# B_to_VM_Protection_Circuit.net
KiCad netlist of a schematic drawn in EAGLE
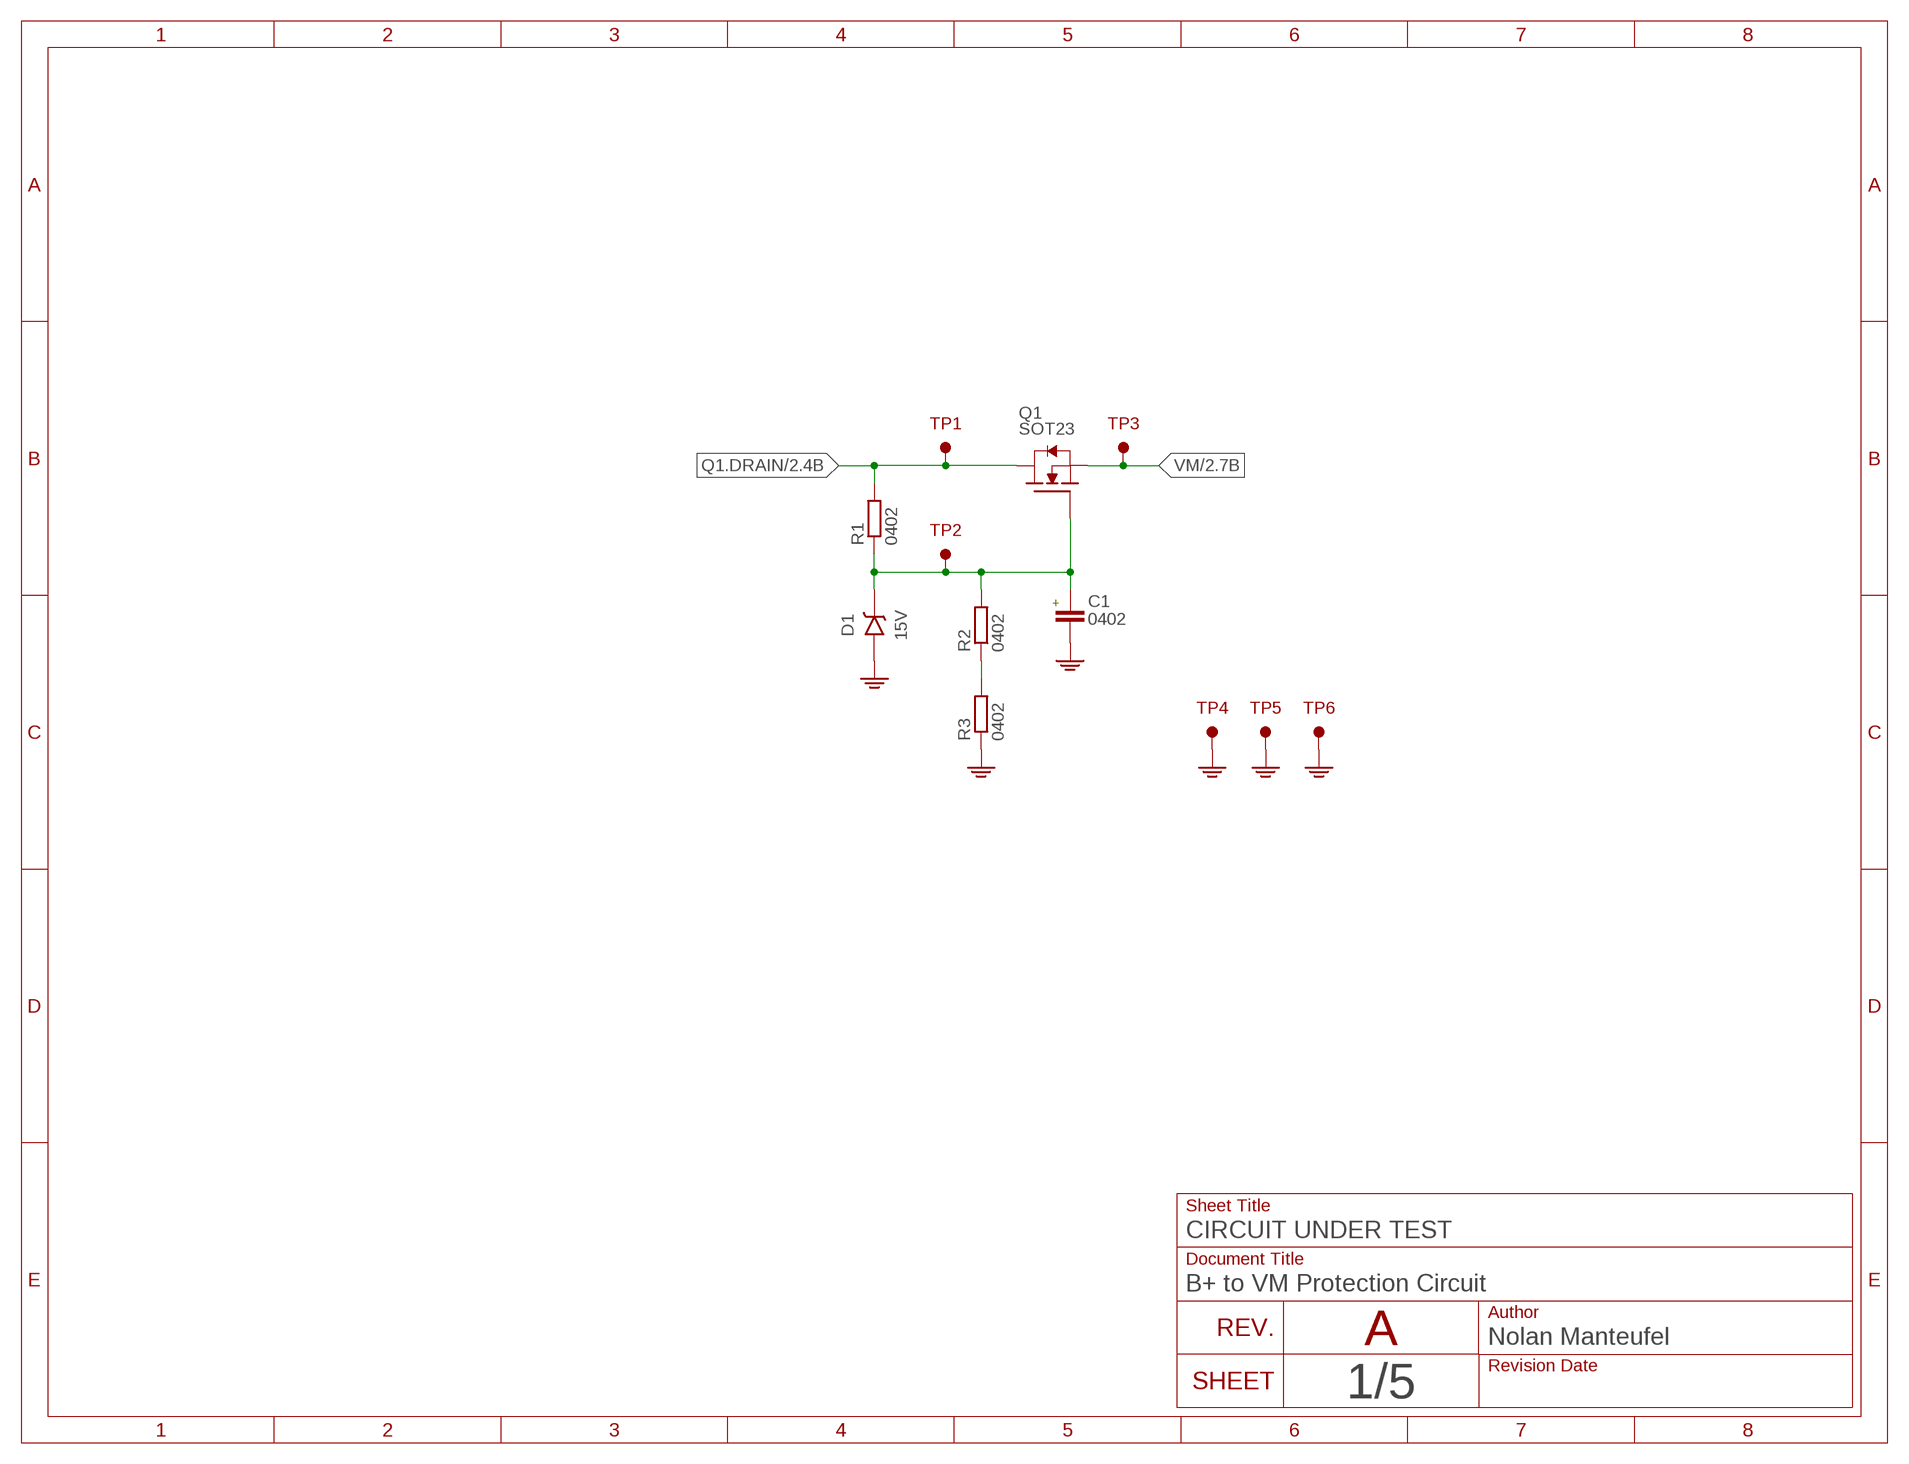
[diagram p0: schematic, sheet 1]
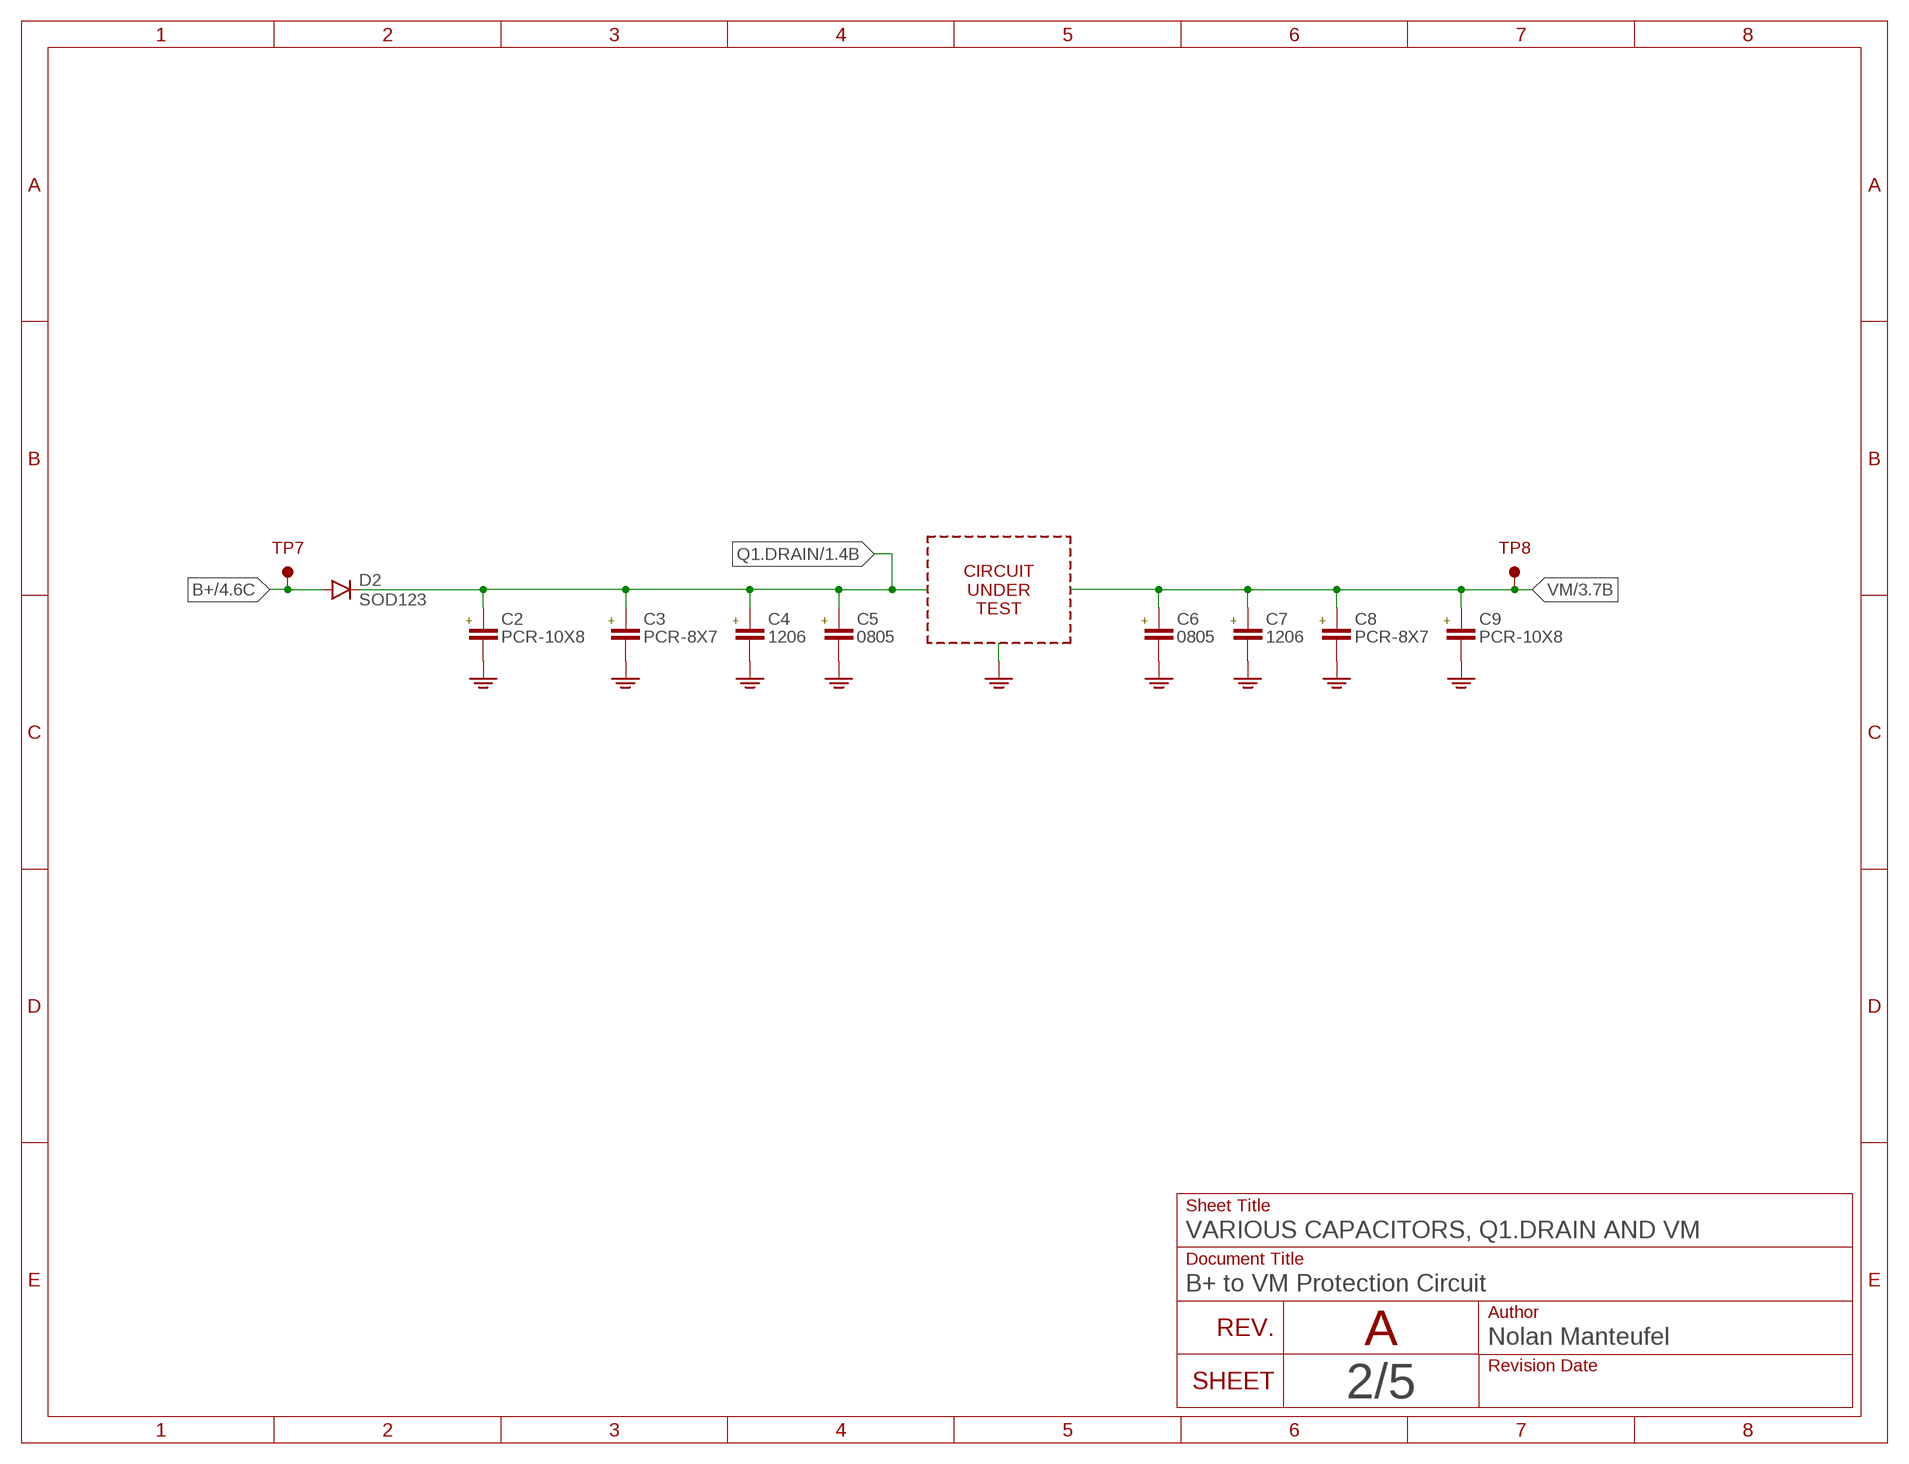
[diagram p1: schematic, sheet 2]
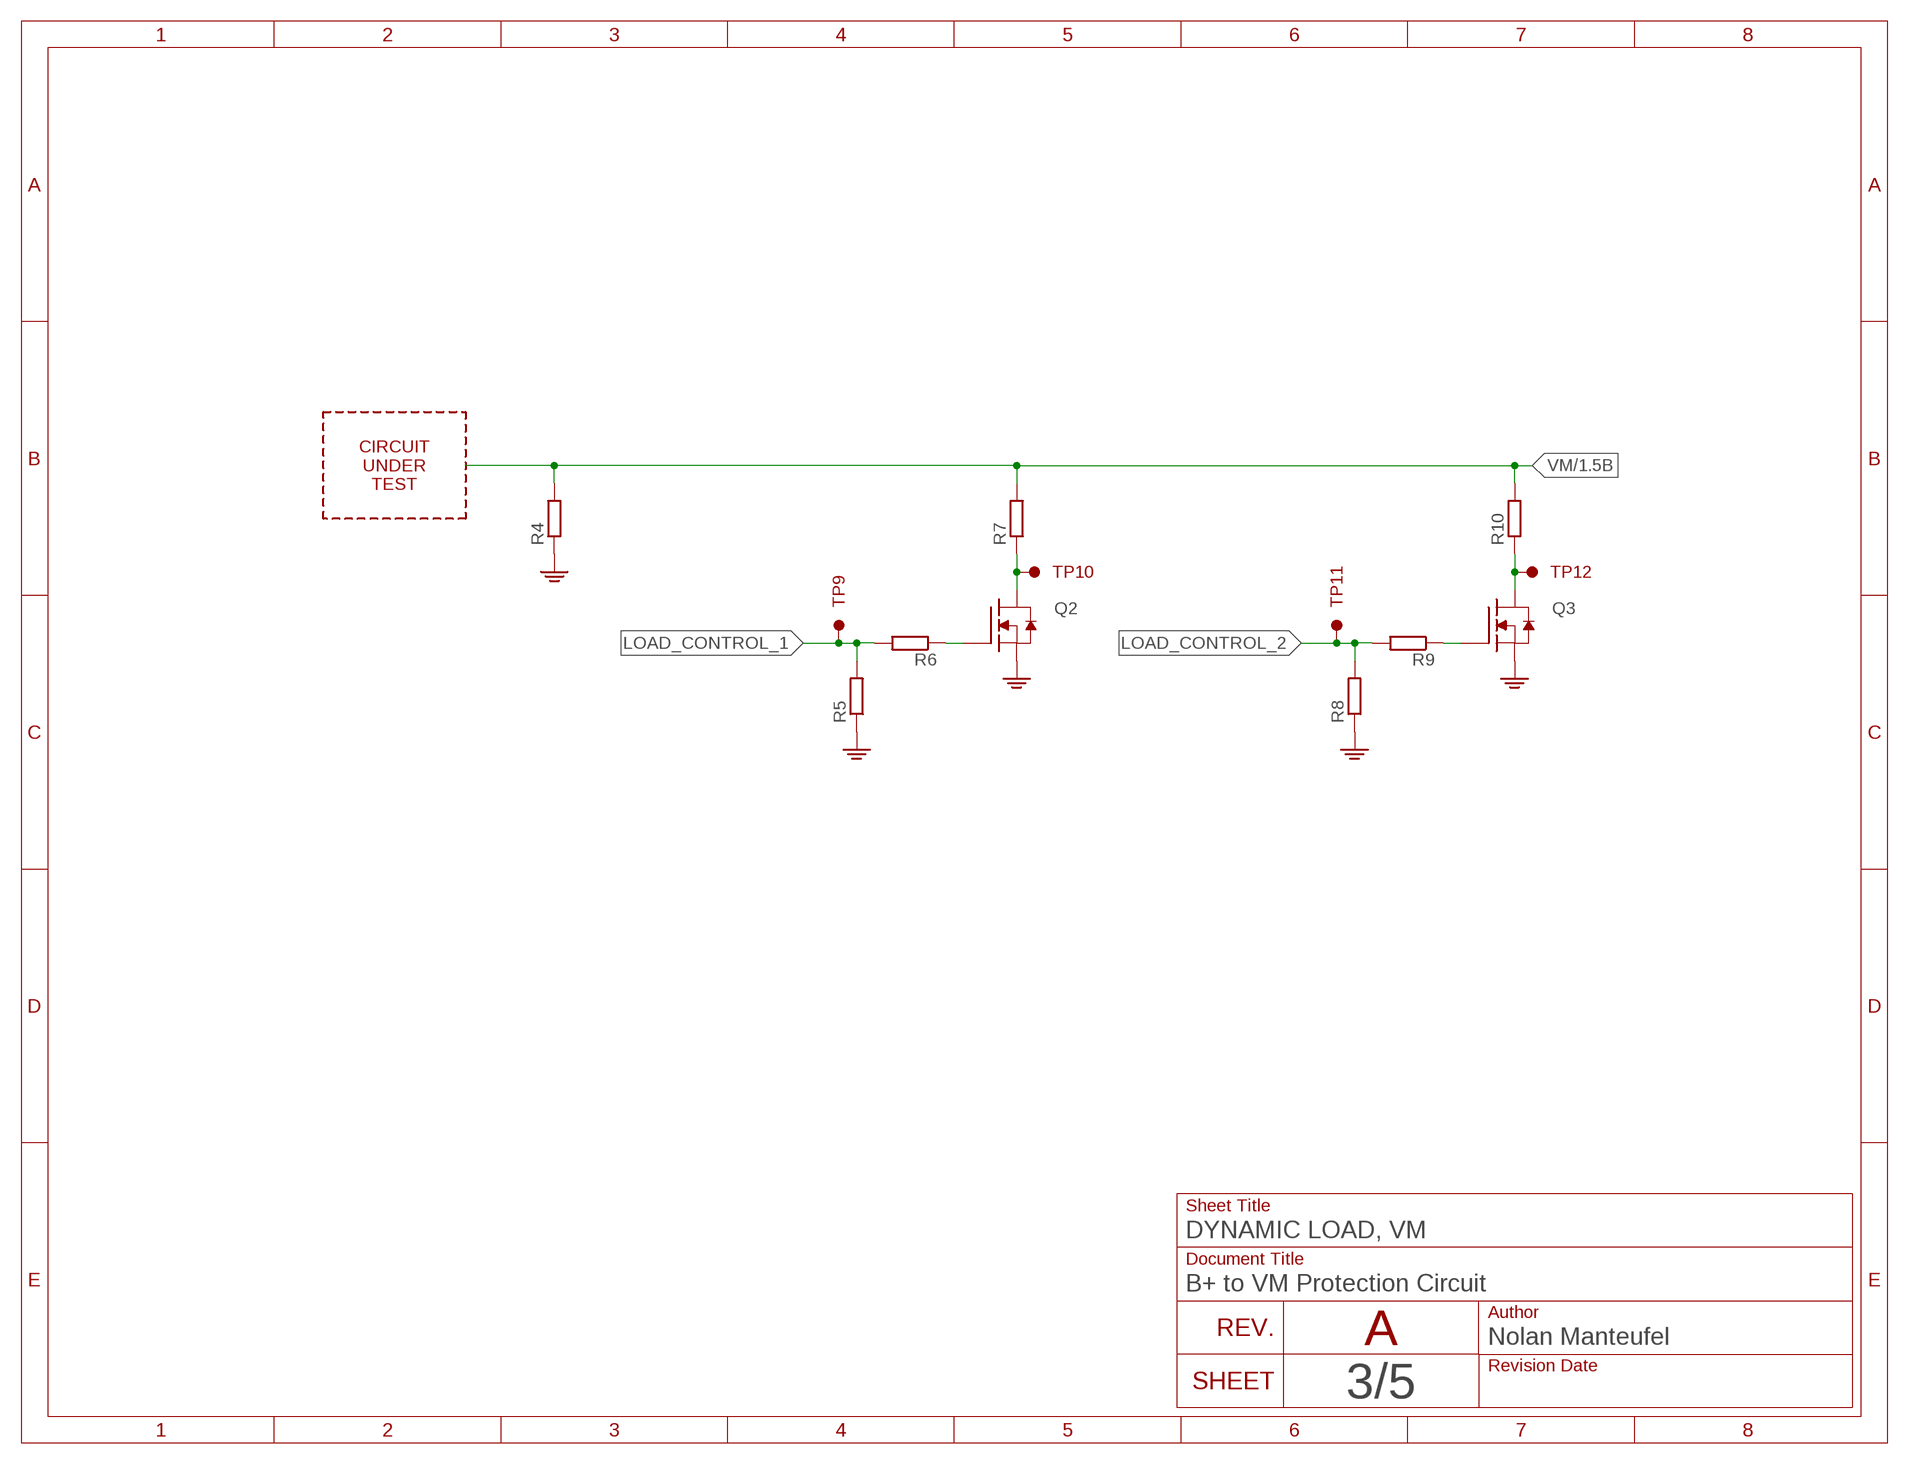
[diagram p2: schematic, sheet 3]
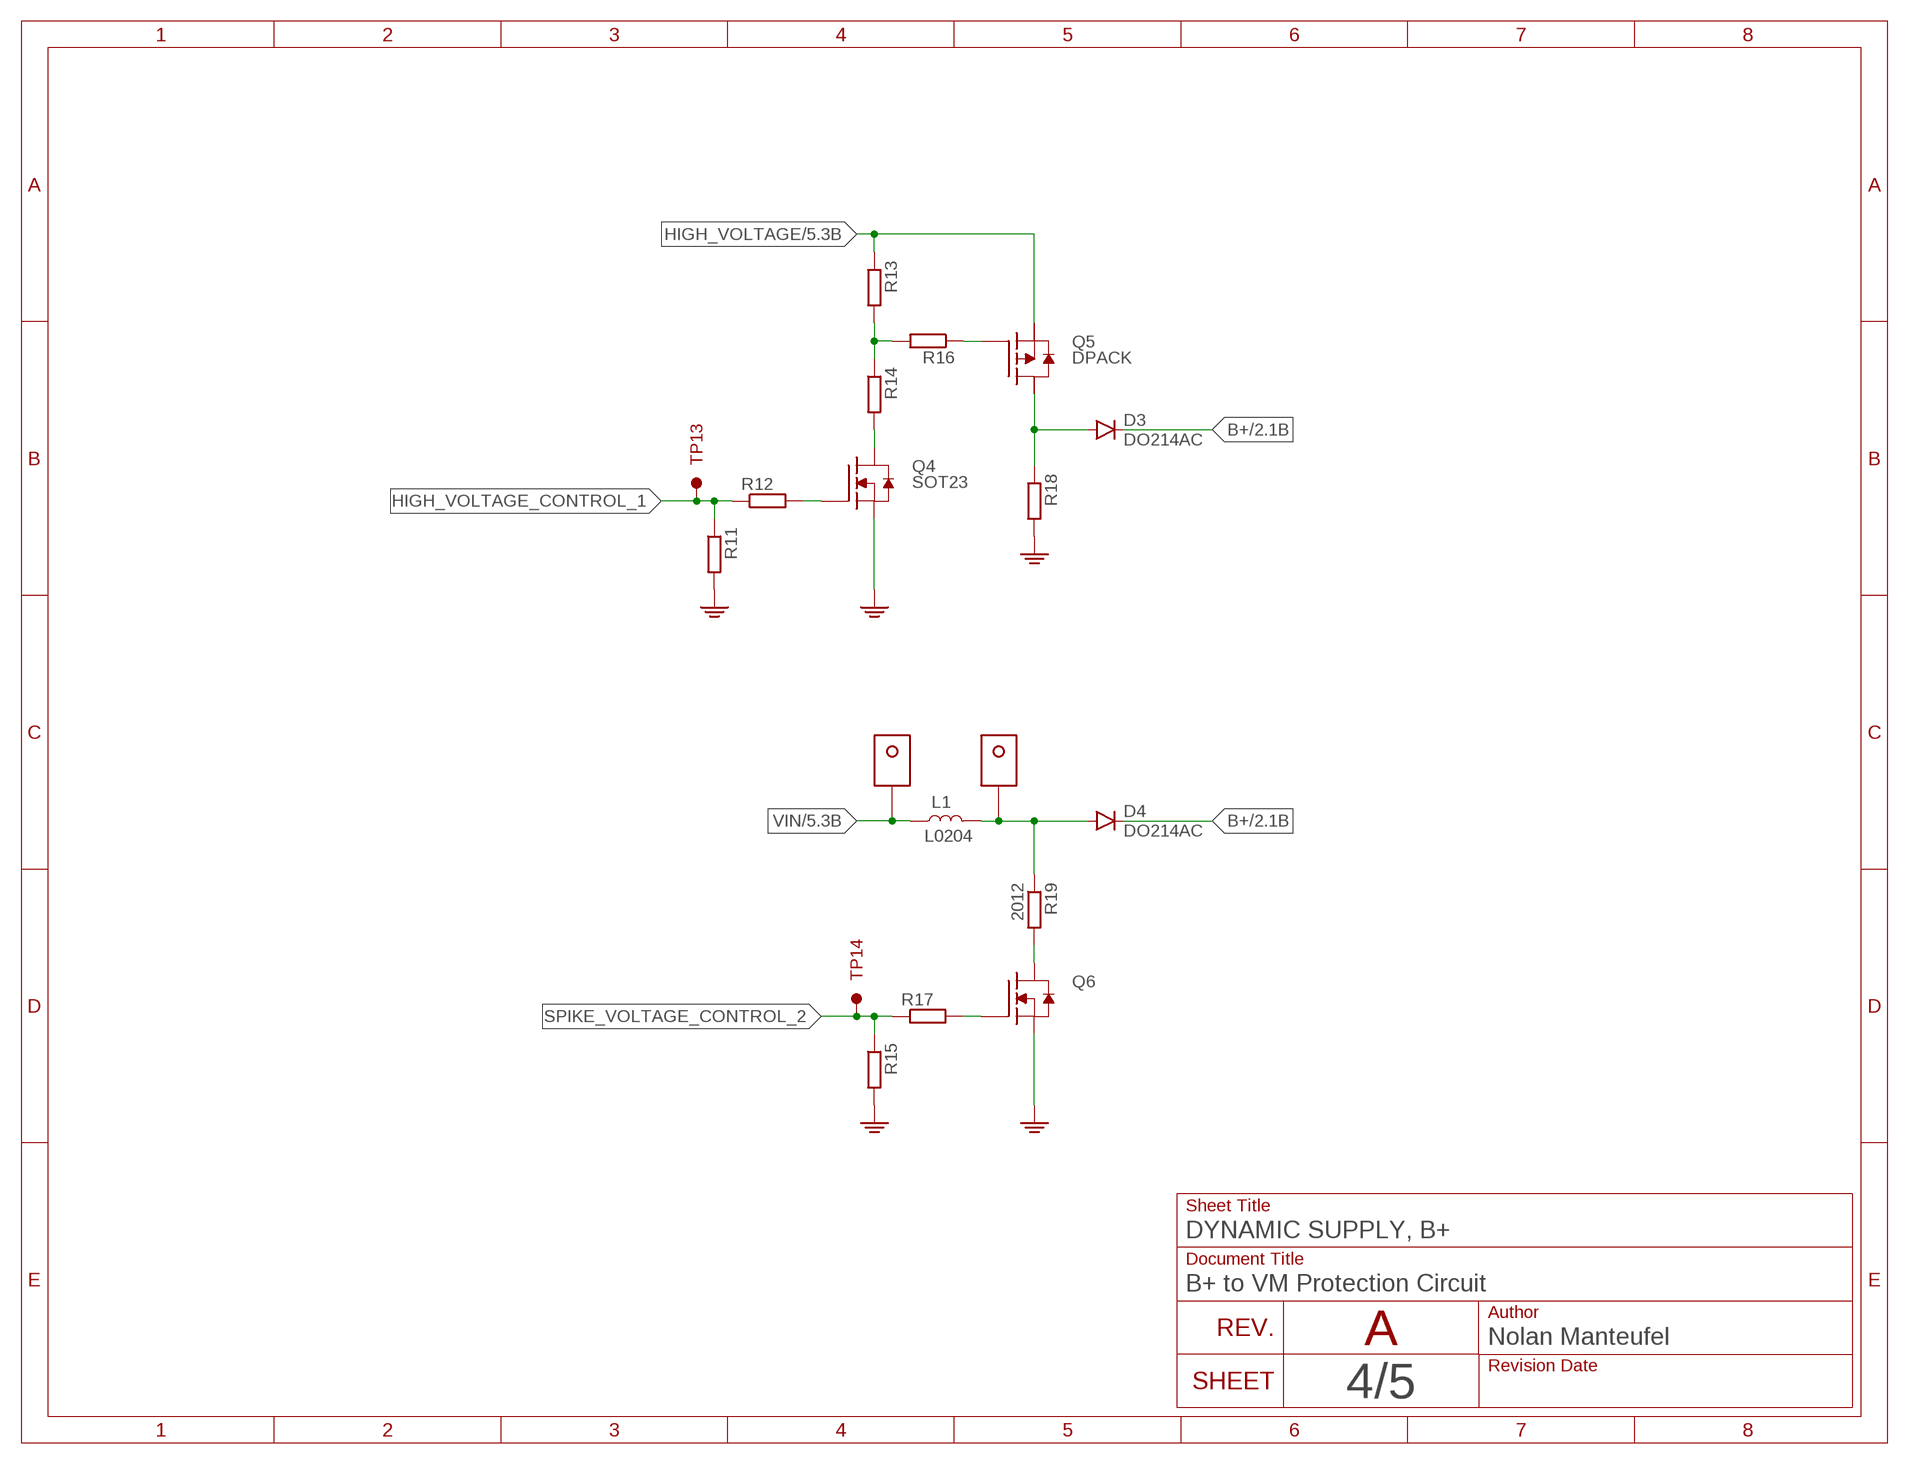
[diagram p3: schematic, sheet 4]
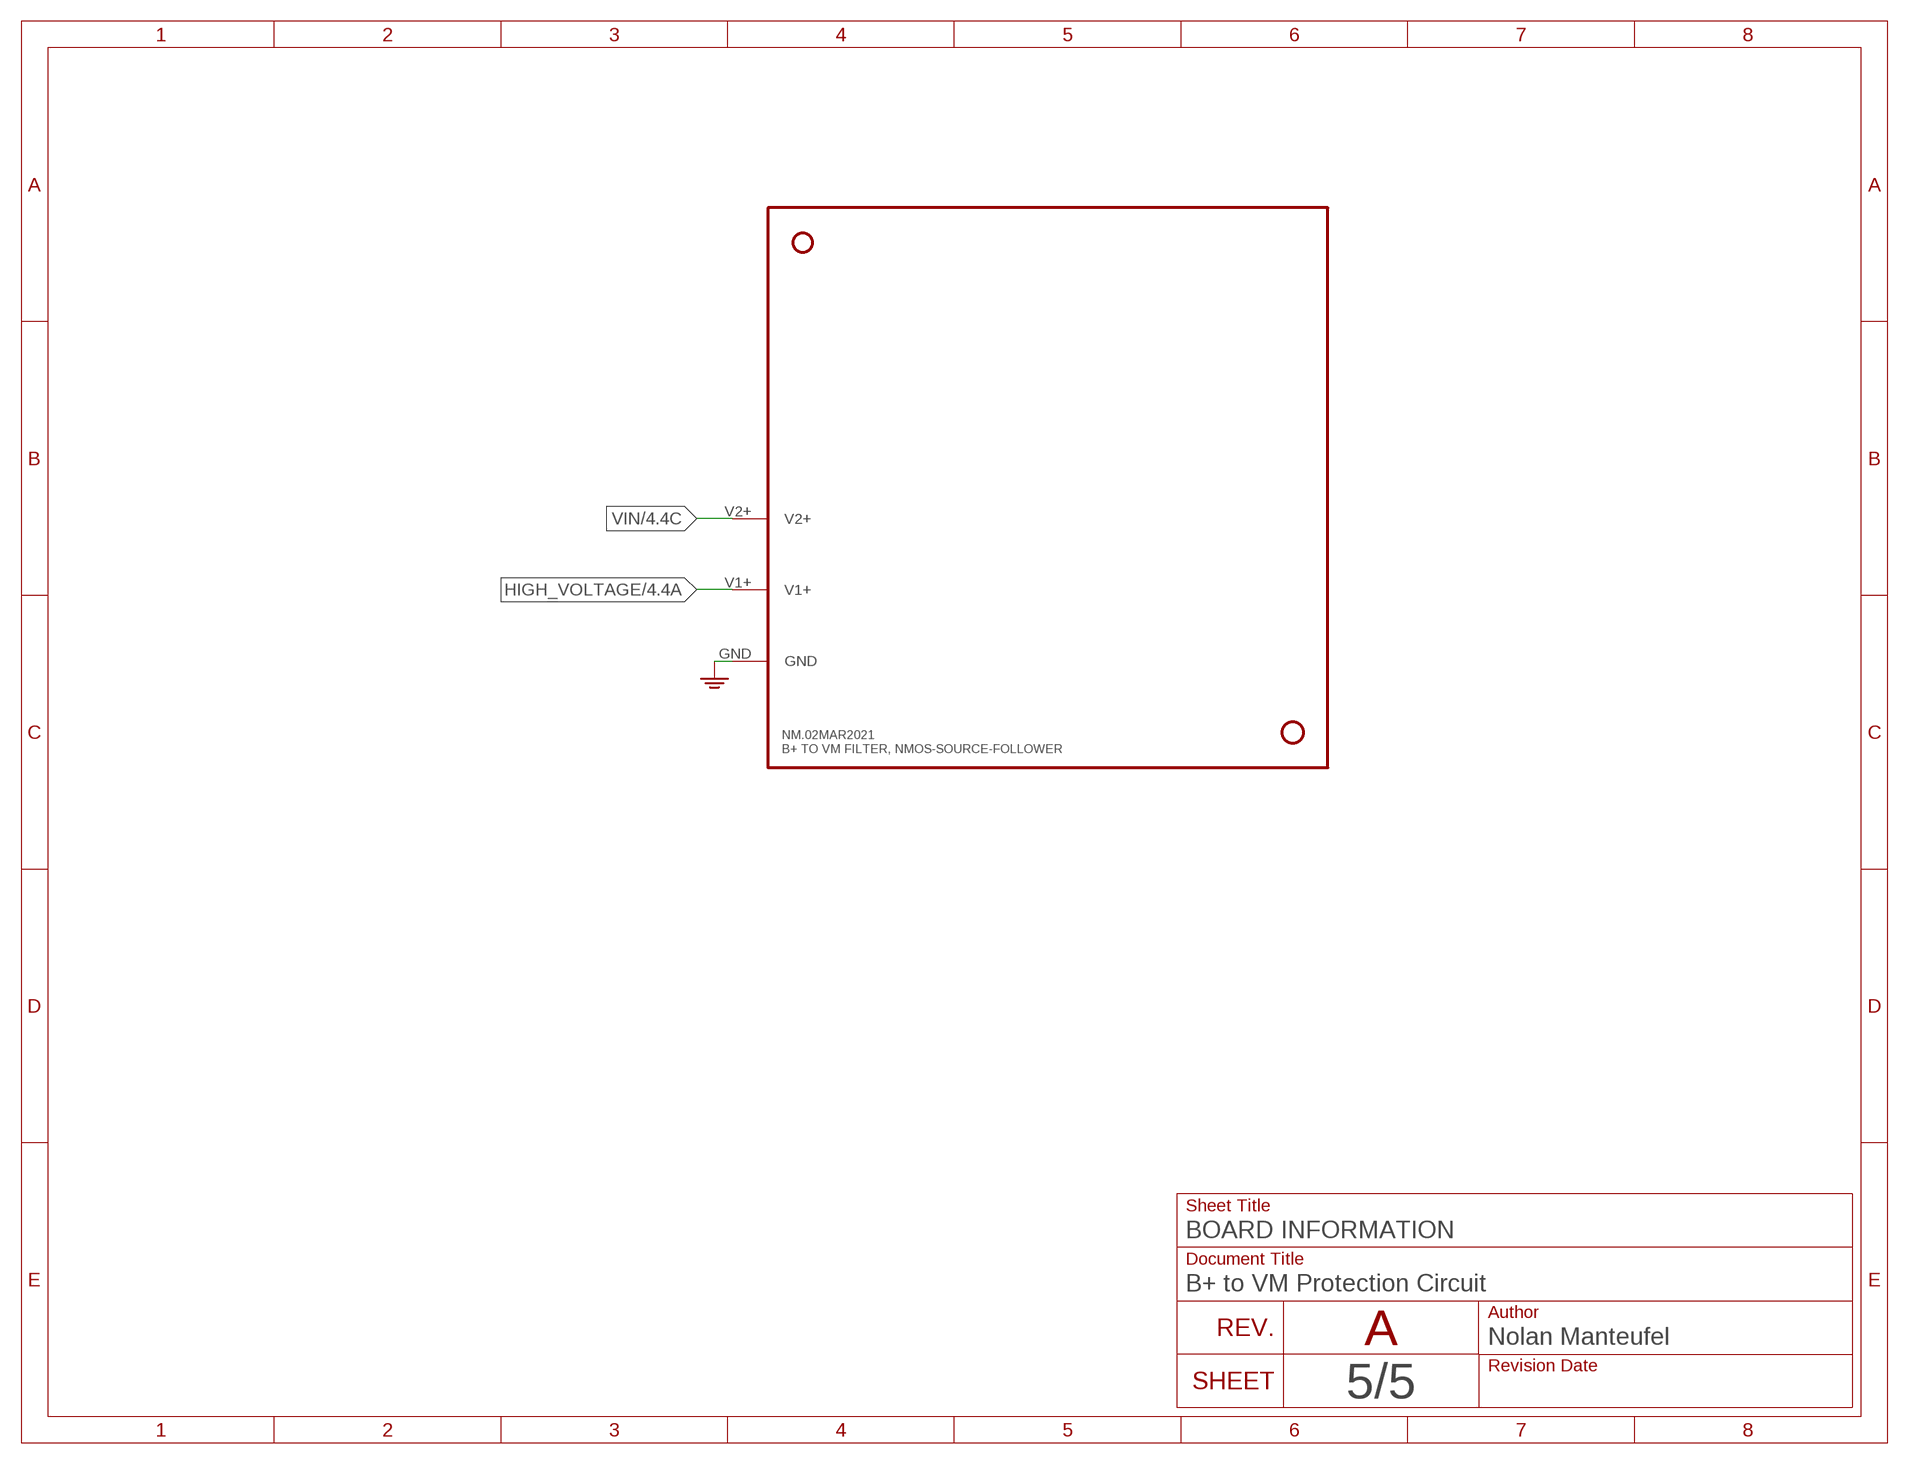
[diagram p4: schematic, sheet 5]

(export (version "E")
  (design (tool "Eeschema 10.0.6"))
  (components
    (comp (ref "C1")
      (value "0402")
      (footprint "eagle-import:C0402")
      (libsource (lib "eagle-import") (part "C-EUC0402"))
    )
    (comp (ref "D1")
      (value "15V")
      (footprint "eagle-import:SOT23")
      (libsource (lib "eagle-import") (part "ZENER-DIODESOT23"))
    )
    (comp (ref "Q1")
      (value "SOT23")
      (footprint "eagle-import:SOT23")
      (libsource (lib "eagle-import") (part "MOSFET-NSOT23"))
    )
    (comp (ref "R1")
      (value "0402")
      (footprint "eagle-import:R0402")
      (libsource (lib "eagle-import") (part "R-EU_R0402"))
    )
    (comp (ref "R2")
      (value "0402")
      (footprint "eagle-import:R0402")
      (libsource (lib "eagle-import") (part "R-EU_R0402"))
    )
    (comp (ref "R3")
      (value "0402")
      (footprint "eagle-import:R0402")
      (libsource (lib "eagle-import") (part "R-EU_R0402"))
    )
    (comp (ref "TP1")
      (value "TESTPOINTKE5000-SMTEXT")
      (footprint "eagle-import:PINS_1_TESTPOINT_KE5000_NOTEXT")
      (libsource (lib "eagle-import") (part "TESTPOINTKE5000-SMTEXT"))
    )
    (comp (ref "TP2")
      (value "TESTPOINTKE5000-SMTEXT")
      (footprint "eagle-import:PINS_1_TESTPOINT_KE5000_NOTEXT")
      (libsource (lib "eagle-import") (part "TESTPOINTKE5000-SMTEXT"))
    )
    (comp (ref "TP3")
      (value "TESTPOINTKE5000-SMTEXT")
      (footprint "eagle-import:PINS_1_TESTPOINT_KE5000_NOTEXT")
      (libsource (lib "eagle-import") (part "TESTPOINTKE5000-SMTEXT"))
    )
    (comp (ref "TP4")
      (value "TESTPOINTKE5000-SMTEXT")
      (footprint "eagle-import:PINS_1_TESTPOINT_KE5000_NOTEXT")
      (libsource (lib "eagle-import") (part "TESTPOINTKE5000-SMTEXT"))
    )
    (comp (ref "TP5")
      (value "TESTPOINTKE5000-SMTEXT")
      (footprint "eagle-import:PINS_1_TESTPOINT_KE5000_NOTEXT")
      (libsource (lib "eagle-import") (part "TESTPOINTKE5000-SMTEXT"))
    )
    (comp (ref "TP6")
      (value "TESTPOINTKE5000-SMTEXT")
      (footprint "eagle-import:PINS_1_TESTPOINT_KE5000_NOTEXT")
      (libsource (lib "eagle-import") (part "TESTPOINTKE5000-SMTEXT"))
    )
    (comp (ref "D3")
      (value "DO214AC")
      (footprint "eagle-import:DO214AC")
      (libsource (lib "eagle-import") (part "DIODE-DO214AC"))
    )
    (comp (ref "D4")
      (value "DO214AC")
      (footprint "eagle-import:DO214AC")
      (libsource (lib "eagle-import") (part "DIODE-DO214AC"))
    )
    (comp (ref "L1")
      (value "L0204")
      (footprint "eagle-import:0204_5")
      (libsource (lib "eagle-import") (part "L0204"))
    )
    (comp (ref "Q4")
      (value "SOT23")
      (footprint "eagle-import:SOT23")
      (libsource (lib "eagle-import") (part "MOSFET-NSOT23"))
    )
    (comp (ref "Q5")
      (value "DPACK")
      (footprint "eagle-import:D-PAK_TO252AA")
      (libsource (lib "eagle-import") (part "MOSFET-PDPAK"))
    )
    (comp (ref "Q6")
      (value "MOSFET-N_NTMFS5C426NT3G")
      (footprint "eagle-import:DFN5")
      (libsource (lib "eagle-import") (part "MOSFET-N_NTMFS5C426NT3G"))
    )
    (comp (ref "R11")
      (value "R-EU_M0805")
      (footprint "eagle-import:M0805")
      (libsource (lib "eagle-import") (part "R-EU_M0805"))
    )
    (comp (ref "R12")
      (value "R-EU_M0805")
      (footprint "eagle-import:M0805")
      (libsource (lib "eagle-import") (part "R-EU_M0805"))
    )
    (comp (ref "R13")
      (value "R-EU_M0805")
      (footprint "eagle-import:M0805")
      (libsource (lib "eagle-import") (part "R-EU_M0805"))
    )
    (comp (ref "R14")
      (value "R-EU_M0805")
      (footprint "eagle-import:M0805")
      (libsource (lib "eagle-import") (part "R-EU_M0805"))
    )
    (comp (ref "R15")
      (value "R-EU_M0805")
      (footprint "eagle-import:M0805")
      (libsource (lib "eagle-import") (part "R-EU_M0805"))
    )
    (comp (ref "R16")
      (value "R-EU_M0805")
      (footprint "eagle-import:M0805")
      (libsource (lib "eagle-import") (part "R-EU_M0805"))
    )
    (comp (ref "R17")
      (value "R-EU_M0805")
      (footprint "eagle-import:M0805")
      (libsource (lib "eagle-import") (part "R-EU_M0805"))
    )
    (comp (ref "R18")
      (value "R-EU_M0805")
      (footprint "eagle-import:M0805")
      (libsource (lib "eagle-import") (part "R-EU_M0805"))
    )
    (comp (ref "R19")
      (value "2012")
      (footprint "eagle-import:R1210")
      (libsource (lib "eagle-import") (part "R-EU_R1210"))
    )
    (comp (ref "TP13")
      (value "TESTPOINTKE5000-SMTEXT")
      (footprint "eagle-import:PINS_1_TESTPOINT_KE5000_NOTEXT")
      (libsource (lib "eagle-import") (part "TESTPOINTKE5000-SMTEXT"))
    )
    (comp (ref "TP14")
      (value "TESTPOINTKE5000-SMTEXT")
      (footprint "eagle-import:PINS_1_TESTPOINT_KE5000_NOTEXT")
      (libsource (lib "eagle-import") (part "TESTPOINTKE5000-SMTEXT"))
    )
    (comp (ref "U$1")
      (value "SPADE-TAB")
      (footprint "eagle-import:SPADE-TAB-6.3MM")
      (libsource (lib "eagle-import") (part "SPADE-TAB"))
    )
    (comp (ref "U$2")
      (value "SPADE-TAB")
      (footprint "eagle-import:SPADE-TAB-6.3MM")
      (libsource (lib "eagle-import") (part "SPADE-TAB"))
    )
    (comp (ref "C2")
      (value "PCR-10X8")
      (footprint "eagle-import:C-PCR-10X8")
      (libsource (lib "eagle-import") (part "C-EUPCR-10X8"))
    )
    (comp (ref "C3")
      (value "PCR-8X7")
      (footprint "eagle-import:C-PCR-8X7")
      (libsource (lib "eagle-import") (part "C-EUPCR-8X7"))
    )
    (comp (ref "C4")
      (value "1206")
      (footprint "eagle-import:C1206")
      (libsource (lib "eagle-import") (part "C-EUC1206"))
    )
    (comp (ref "C5")
      (value "0805")
      (footprint "eagle-import:C0805")
      (libsource (lib "eagle-import") (part "C-EUC0805"))
    )
    (comp (ref "C6")
      (value "0805")
      (footprint "eagle-import:C0805")
      (libsource (lib "eagle-import") (part "C-EUC0805"))
    )
    (comp (ref "C7")
      (value "1206")
      (footprint "eagle-import:C1206")
      (libsource (lib "eagle-import") (part "C-EUC1206"))
    )
    (comp (ref "C8")
      (value "PCR-8X7")
      (footprint "eagle-import:C-PCR-8X7")
      (libsource (lib "eagle-import") (part "C-EUPCR-8X7"))
    )
    (comp (ref "C9")
      (value "PCR-10X8")
      (footprint "eagle-import:C-PCR-10X8")
      (libsource (lib "eagle-import") (part "C-EUPCR-10X8"))
    )
    (comp (ref "D2")
      (value "SOD123")
      (footprint "eagle-import:SOD123")
      (libsource (lib "eagle-import") (part "DIODE-SOD123"))
    )
    (comp (ref "TP7")
      (value "TESTPOINTKE5000-SMTEXT")
      (footprint "eagle-import:PINS_1_TESTPOINT_KE5000_NOTEXT")
      (libsource (lib "eagle-import") (part "TESTPOINTKE5000-SMTEXT"))
    )
    (comp (ref "TP8")
      (value "TESTPOINTKE5000-SMTEXT")
      (footprint "eagle-import:PINS_1_TESTPOINT_KE5000_NOTEXT")
      (libsource (lib "eagle-import") (part "TESTPOINTKE5000-SMTEXT"))
    )
    (comp (ref "NM.02MAR2021")
      (value "B+ TO VM FILTER, NMOS-SOURCE-FOLLOWER")
      (footprint "eagle-import:EVAL-80X80")
      (libsource (lib "eagle-import") (part "PCB_EVAL_80X80"))
    )
    (comp (ref "Q2")
      (value "MOSFET-N_NTMFS5C426NT3G")
      (footprint "eagle-import:DFN5")
      (libsource (lib "eagle-import") (part "MOSFET-N_NTMFS5C426NT3G"))
    )
    (comp (ref "Q3")
      (value "MOSFET-N_NTMFS5C426NT3G")
      (footprint "eagle-import:DFN5")
      (libsource (lib "eagle-import") (part "MOSFET-N_NTMFS5C426NT3G"))
    )
    (comp (ref "R4")
      (value "R-EU_0207/10")
      (footprint "eagle-import:0207_10")
      (libsource (lib "eagle-import") (part "R-EU_0207/10"))
    )
    (comp (ref "R5")
      (value "R-EU_M0805")
      (footprint "eagle-import:M0805")
      (libsource (lib "eagle-import") (part "R-EU_M0805"))
    )
    (comp (ref "R6")
      (value "R-EU_M0805")
      (footprint "eagle-import:M0805")
      (libsource (lib "eagle-import") (part "R-EU_M0805"))
    )
    (comp (ref "R7")
      (value "R-EU_0207/10")
      (footprint "eagle-import:0207_10")
      (libsource (lib "eagle-import") (part "R-EU_0207/10"))
    )
    (comp (ref "R8")
      (value "R-EU_M0805")
      (footprint "eagle-import:M0805")
      (libsource (lib "eagle-import") (part "R-EU_M0805"))
    )
    (comp (ref "R9")
      (value "R-EU_M0805")
      (footprint "eagle-import:M0805")
      (libsource (lib "eagle-import") (part "R-EU_M0805"))
    )
    (comp (ref "R10")
      (value "R-EU_0207/10")
      (footprint "eagle-import:0207_10")
      (libsource (lib "eagle-import") (part "R-EU_0207/10"))
    )
    (comp (ref "TP9")
      (value "TESTPOINTKE5000-SMTEXT")
      (footprint "eagle-import:PINS_1_TESTPOINT_KE5000_NOTEXT")
      (libsource (lib "eagle-import") (part "TESTPOINTKE5000-SMTEXT"))
    )
    (comp (ref "TP10")
      (value "TESTPOINTKE5000-SMTEXT")
      (footprint "eagle-import:PINS_1_TESTPOINT_KE5000_NOTEXT")
      (libsource (lib "eagle-import") (part "TESTPOINTKE5000-SMTEXT"))
    )
    (comp (ref "TP11")
      (value "TESTPOINTKE5000-SMTEXT")
      (footprint "eagle-import:PINS_1_TESTPOINT_KE5000_NOTEXT")
      (libsource (lib "eagle-import") (part "TESTPOINTKE5000-SMTEXT"))
    )
    (comp (ref "TP12")
      (value "TESTPOINTKE5000-SMTEXT")
      (footprint "eagle-import:PINS_1_TESTPOINT_KE5000_NOTEXT")
      (libsource (lib "eagle-import") (part "TESTPOINTKE5000-SMTEXT"))
    )
  )
  (nets
    (net (code "1") (name "B+") (class "Default")
      (node (ref "D2") (pin "A") (pinfunction "A_A") (pintype "passive"))
      (node (ref "D3") (pin "C") (pinfunction "C_C") (pintype "passive"))
      (node (ref "D4") (pin "C") (pinfunction "C_C") (pintype "passive"))
      (node (ref "TP7") (pin "1") (pinfunction "1_1") (pintype "bidirectional"))
    )
    (net (code "2") (name "GND") (class "Default")
      (node (ref "C1") (pin "2") (pinfunction "2_2") (pintype "passive"))
      (node (ref "C2") (pin "-") (pinfunction "2_-") (pintype "passive"))
      (node (ref "C3") (pin "-") (pinfunction "2_-") (pintype "passive"))
      (node (ref "C4") (pin "-") (pinfunction "2_-") (pintype "passive"))
      (node (ref "C5") (pin "2") (pinfunction "2_2") (pintype "passive"))
      (node (ref "C6") (pin "2") (pinfunction "2_2") (pintype "passive"))
      (node (ref "C7") (pin "-") (pinfunction "2_-") (pintype "passive"))
      (node (ref "C8") (pin "-") (pinfunction "2_-") (pintype "passive"))
      (node (ref "C9") (pin "-") (pinfunction "2_-") (pintype "passive"))
      (node (ref "D1") (pin "1") (pinfunction "A_1") (pintype "passive"))
      (node (ref "NM.02MAR2021") (pin "GND") (pinfunction "GND_GND") (pintype "bidirectional"))
      (node (ref "Q2") (pin "1") (pinfunction "S_1") (pintype "passive"))
      (node (ref "Q2") (pin "2") (pinfunction "S_2") (pintype "passive"))
      (node (ref "Q2") (pin "3") (pinfunction "S_3") (pintype "passive"))
      (node (ref "Q3") (pin "1") (pinfunction "S_1") (pintype "passive"))
      (node (ref "Q3") (pin "2") (pinfunction "S_2") (pintype "passive"))
      (node (ref "Q3") (pin "3") (pinfunction "S_3") (pintype "passive"))
      (node (ref "Q4") (pin "2") (pinfunction "S_2") (pintype "passive"))
      (node (ref "Q6") (pin "1") (pinfunction "S_1") (pintype "passive"))
      (node (ref "Q6") (pin "2") (pinfunction "S_2") (pintype "passive"))
      (node (ref "Q6") (pin "3") (pinfunction "S_3") (pintype "passive"))
      (node (ref "R11") (pin "2") (pinfunction "2_2") (pintype "passive"))
      (node (ref "R15") (pin "2") (pinfunction "2_2") (pintype "passive"))
      (node (ref "R18") (pin "2") (pinfunction "2_2") (pintype "passive"))
      (node (ref "R3") (pin "1") (pinfunction "1_1") (pintype "passive"))
      (node (ref "R4") (pin "1") (pinfunction "1_1") (pintype "passive"))
      (node (ref "R5") (pin "1") (pinfunction "1_1") (pintype "passive"))
      (node (ref "R8") (pin "1") (pinfunction "1_1") (pintype "passive"))
      (node (ref "TP4") (pin "1") (pinfunction "1_1") (pintype "bidirectional"))
      (node (ref "TP5") (pin "1") (pinfunction "1_1") (pintype "bidirectional"))
      (node (ref "TP6") (pin "1") (pinfunction "1_1") (pintype "bidirectional"))
    )
    (net (code "3") (name "HIGH_VOLTAGE") (class "Default")
      (node (ref "NM.02MAR2021") (pin "V1+") (pinfunction "V1+_V1+") (pintype "bidirectional"))
      (node (ref "Q5") (pin "4") (pinfunction "S_4") (pintype "passive"))
      (node (ref "R13") (pin "1") (pinfunction "1_1") (pintype "passive"))
    )
    (net (code "4") (name "HIGH_VOLTAGE_CONTROL_1") (class "Default")
      (node (ref "R11") (pin "1") (pinfunction "1_1") (pintype "passive"))
      (node (ref "R12") (pin "1") (pinfunction "1_1") (pintype "passive"))
      (node (ref "TP13") (pin "1") (pinfunction "1_1") (pintype "bidirectional"))
    )
    (net (code "5") (name "LOAD_CONTROL_1") (class "Default")
      (node (ref "R5") (pin "2") (pinfunction "2_2") (pintype "passive"))
      (node (ref "R6") (pin "2") (pinfunction "2_2") (pintype "passive"))
      (node (ref "TP9") (pin "1") (pinfunction "1_1") (pintype "bidirectional"))
    )
    (net (code "6") (name "LOAD_CONTROL_2") (class "Default")
      (node (ref "R8") (pin "2") (pinfunction "2_2") (pintype "passive"))
      (node (ref "R9") (pin "2") (pinfunction "2_2") (pintype "passive"))
      (node (ref "TP11") (pin "1") (pinfunction "1_1") (pintype "bidirectional"))
    )
    (net (code "7") (name "Net-(D1-C)") (class "Default")
      (node (ref "C1") (pin "1") (pinfunction "1_1") (pintype "passive"))
      (node (ref "D1") (pin "3") (pinfunction "C_3") (pintype "passive"))
      (node (ref "Q1") (pin "1") (pinfunction "G_1") (pintype "passive"))
      (node (ref "R1") (pin "1") (pinfunction "1_1") (pintype "passive"))
      (node (ref "R2") (pin "2") (pinfunction "2_2") (pintype "passive"))
      (node (ref "TP2") (pin "1") (pinfunction "1_1") (pintype "bidirectional"))
    )
    (net (code "8") (name "Net-(L1-P$2)") (class "Default")
      (node (ref "D4") (pin "A") (pinfunction "A_A") (pintype "passive"))
      (node (ref "L1") (pin "2") (pinfunction "P$2_2") (pintype "passive"))
      (node (ref "R19") (pin "1") (pinfunction "1_1") (pintype "passive"))
      (node (ref "U$2") (pin "P$1") (pinfunction "P$1_P$1") (pintype "bidirectional"))
      (node (ref "U$2") (pin "P$2") (pinfunction "P$1_P$2") (pintype "bidirectional"))
    )
    (net (code "9") (name "Net-(Q2-D)") (class "Default")
      (node (ref "Q2") (pin "5") (pinfunction "D_5") (pintype "passive"))
      (node (ref "R7") (pin "1") (pinfunction "1_1") (pintype "passive"))
      (node (ref "TP10") (pin "1") (pinfunction "1_1") (pintype "bidirectional"))
    )
    (net (code "10") (name "Net-(Q2-G)") (class "Default")
      (node (ref "Q2") (pin "4") (pinfunction "G_4") (pintype "passive"))
      (node (ref "R6") (pin "1") (pinfunction "1_1") (pintype "passive"))
    )
    (net (code "11") (name "Net-(Q3-D)") (class "Default")
      (node (ref "Q3") (pin "5") (pinfunction "D_5") (pintype "passive"))
      (node (ref "R10") (pin "1") (pinfunction "1_1") (pintype "passive"))
      (node (ref "TP12") (pin "1") (pinfunction "1_1") (pintype "bidirectional"))
    )
    (net (code "12") (name "Net-(Q3-G)") (class "Default")
      (node (ref "Q3") (pin "4") (pinfunction "G_4") (pintype "passive"))
      (node (ref "R9") (pin "1") (pinfunction "1_1") (pintype "passive"))
    )
    (net (code "13") (name "Net-(Q4-D)") (class "Default")
      (node (ref "Q4") (pin "3") (pinfunction "D_3") (pintype "passive"))
      (node (ref "R14") (pin "2") (pinfunction "2_2") (pintype "passive"))
    )
    (net (code "14") (name "Net-(Q4-G)") (class "Default")
      (node (ref "Q4") (pin "1") (pinfunction "G_1") (pintype "passive"))
      (node (ref "R12") (pin "2") (pinfunction "2_2") (pintype "passive"))
    )
    (net (code "15") (name "Net-(Q5-D)") (class "Default")
      (node (ref "D3") (pin "A") (pinfunction "A_A") (pintype "passive"))
      (node (ref "Q5") (pin "3") (pinfunction "D_3") (pintype "passive"))
      (node (ref "R18") (pin "1") (pinfunction "1_1") (pintype "passive"))
    )
    (net (code "16") (name "Net-(Q5-G)") (class "Default")
      (node (ref "Q5") (pin "1") (pinfunction "G_1") (pintype "passive"))
      (node (ref "R16") (pin "1") (pinfunction "1_1") (pintype "passive"))
    )
    (net (code "17") (name "Net-(Q6-D)") (class "Default")
      (node (ref "Q6") (pin "5") (pinfunction "D_5") (pintype "passive"))
      (node (ref "R19") (pin "2") (pinfunction "2_2") (pintype "passive"))
    )
    (net (code "18") (name "Net-(Q6-G)") (class "Default")
      (node (ref "Q6") (pin "4") (pinfunction "G_4") (pintype "passive"))
      (node (ref "R17") (pin "2") (pinfunction "2_2") (pintype "passive"))
    )
    (net (code "19") (name "Net-(R2-Pad1)") (class "Default")
      (node (ref "R2") (pin "1") (pinfunction "1_1") (pintype "passive"))
      (node (ref "R3") (pin "2") (pinfunction "2_2") (pintype "passive"))
    )
    (net (code "20") (name "Net-(R13-Pad2)") (class "Default")
      (node (ref "R13") (pin "2") (pinfunction "2_2") (pintype "passive"))
      (node (ref "R14") (pin "1") (pinfunction "1_1") (pintype "passive"))
      (node (ref "R16") (pin "2") (pinfunction "2_2") (pintype "passive"))
    )
    (net (code "21") (name "Q1.DRAIN") (class "Default")
      (node (ref "C2") (pin "+") (pinfunction "1_+") (pintype "passive"))
      (node (ref "C3") (pin "+") (pinfunction "1_+") (pintype "passive"))
      (node (ref "C4") (pin "+") (pinfunction "1_+") (pintype "passive"))
      (node (ref "C5") (pin "1") (pinfunction "1_1") (pintype "passive"))
      (node (ref "D2") (pin "C") (pinfunction "C_C") (pintype "passive"))
      (node (ref "Q1") (pin "3") (pinfunction "D_3") (pintype "passive"))
      (node (ref "R1") (pin "2") (pinfunction "2_2") (pintype "passive"))
      (node (ref "TP1") (pin "1") (pinfunction "1_1") (pintype "bidirectional"))
    )
    (net (code "22") (name "SPIKE_VOLTAGE_CONTROL_2") (class "Default")
      (node (ref "R15") (pin "1") (pinfunction "1_1") (pintype "passive"))
      (node (ref "R17") (pin "1") (pinfunction "1_1") (pintype "passive"))
      (node (ref "TP14") (pin "1") (pinfunction "1_1") (pintype "bidirectional"))
    )
    (net (code "23") (name "VIN") (class "Default")
      (node (ref "L1") (pin "1") (pinfunction "P$1_1") (pintype "passive"))
      (node (ref "NM.02MAR2021") (pin "V2+") (pinfunction "V2+_V2+") (pintype "bidirectional"))
      (node (ref "U$1") (pin "P$1") (pinfunction "P$1_P$1") (pintype "bidirectional"))
      (node (ref "U$1") (pin "P$2") (pinfunction "P$1_P$2") (pintype "bidirectional"))
    )
    (net (code "24") (name "VM") (class "Default")
      (node (ref "C6") (pin "1") (pinfunction "1_1") (pintype "passive"))
      (node (ref "C7") (pin "+") (pinfunction "1_+") (pintype "passive"))
      (node (ref "C8") (pin "+") (pinfunction "1_+") (pintype "passive"))
      (node (ref "C9") (pin "+") (pinfunction "1_+") (pintype "passive"))
      (node (ref "Q1") (pin "2") (pinfunction "S_2") (pintype "passive"))
      (node (ref "R10") (pin "2") (pinfunction "2_2") (pintype "passive"))
      (node (ref "R4") (pin "2") (pinfunction "2_2") (pintype "passive"))
      (node (ref "R7") (pin "2") (pinfunction "2_2") (pintype "passive"))
      (node (ref "TP3") (pin "1") (pinfunction "1_1") (pintype "bidirectional"))
      (node (ref "TP8") (pin "1") (pinfunction "1_1") (pintype "bidirectional"))
    )
  )
)
